# HTS221TR.net
KiCad netlist of a schematic drawn in EAGLE
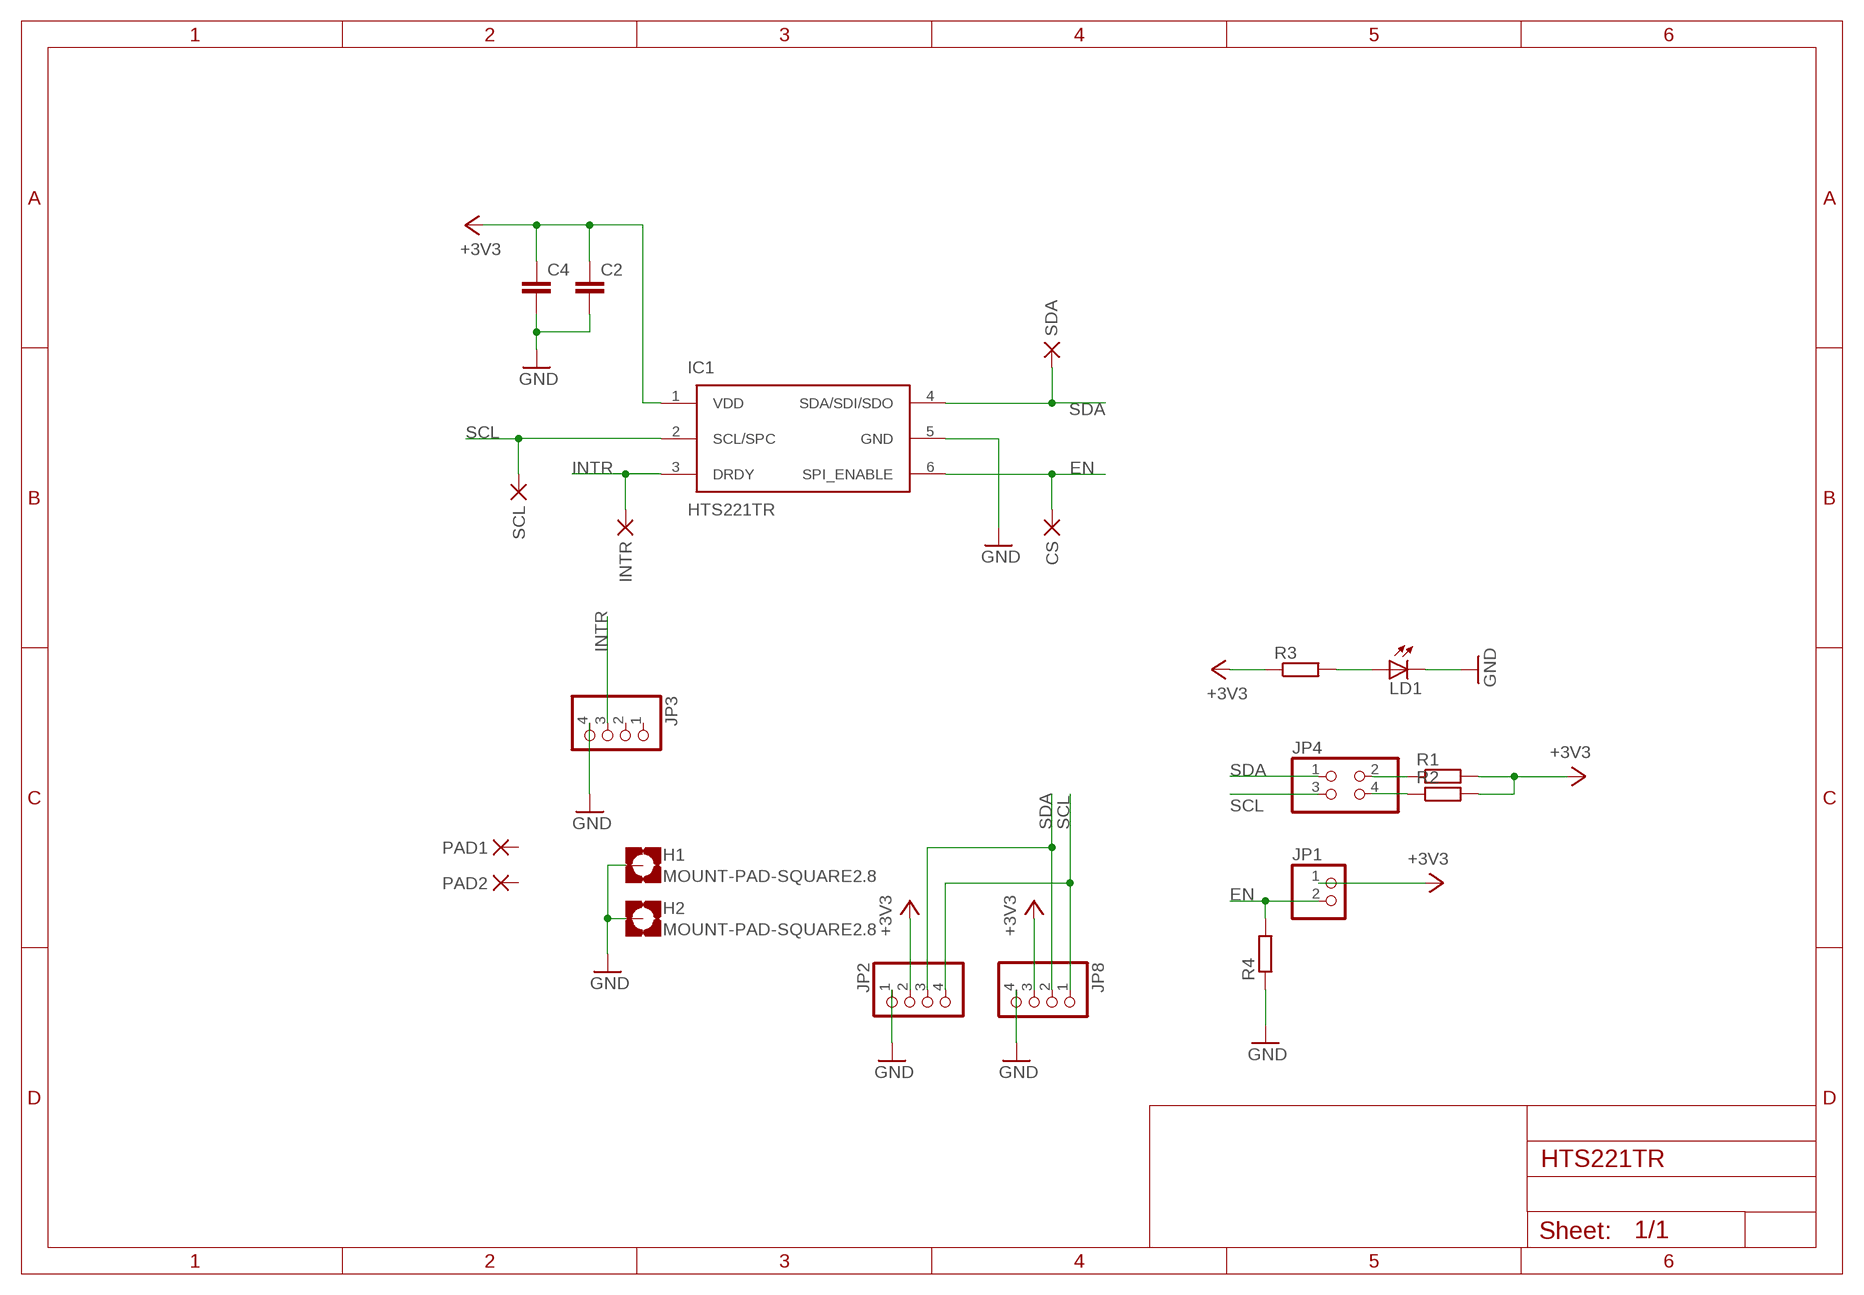
[diagram p0: schematic, sheet 1]

(export (version "E")
  (design (tool "Eeschema 10.0.6"))
  (components
    (comp (ref "C2")
      (value "C-EUC0805")
      (footprint "eagle-import:C0805")
      (libsource (lib "eagle-import") (part "C-EUC0805"))
    )
    (comp (ref "C4")
      (value "C-EUC0805")
      (footprint "eagle-import:C0805")
      (libsource (lib "eagle-import") (part "C-EUC0805"))
    )
    (comp (ref "CS")
      (value "PAD-SMD10R")
      (footprint "eagle-import:SMD10R")
      (libsource (lib "eagle-import") (part "PAD-SMD10R"))
    )
    (comp (ref "H1")
      (value "MOUNT-PAD-SQUARE2.8")
      (footprint "eagle-import:2,8-PAD-SQUARE")
      (libsource (lib "eagle-import") (part "MOUNT-PAD-SQUARE2.8"))
    )
    (comp (ref "H2")
      (value "MOUNT-PAD-SQUARE2.8")
      (footprint "eagle-import:2,8-PAD-SQUARE")
      (libsource (lib "eagle-import") (part "MOUNT-PAD-SQUARE2.8"))
    )
    (comp (ref "IC1")
      (value "HTS221TR")
      (footprint "eagle-import:HLGA-6L")
      (fields (field (name "MOUSER_PART_NUMBER") "511-HTS221TR") (field (name "RS_PART_NUMBER") "1660935"))
      (libsource (lib "eagle-import") (part "HTS221TR"))
    )
    (comp (ref "INTR")
      (value "PAD-SMD10R")
      (footprint "eagle-import:SMD10R")
      (libsource (lib "eagle-import") (part "PAD-SMD10R"))
    )
    (comp (ref "JP1")
      (value "PINHD-1X2")
      (footprint "eagle-import:1X02")
      (libsource (lib "eagle-import") (part "PINHD-1X2"))
    )
    (comp (ref "JP2")
      (value "PINHD-1X4_2.54-90°")
      (footprint "eagle-import:1X04_90")
      (libsource (lib "eagle-import") (part "PINHD-1X4_2.54-90°"))
    )
    (comp (ref "JP3")
      (value "PINHD-1X4")
      (footprint "eagle-import:1X04")
      (libsource (lib "eagle-import") (part "PINHD-1X4"))
    )
    (comp (ref "JP4")
      (value "PINHD-2X2_2.54")
      (footprint "eagle-import:2X02")
      (libsource (lib "eagle-import") (part "PINHD-2X2_2.54"))
    )
    (comp (ref "JP8")
      (value "PINHD-1X4_2.54-90°")
      (footprint "eagle-import:1X04_90")
      (libsource (lib "eagle-import") (part "PINHD-1X4_2.54-90°"))
    )
    (comp (ref "LD1")
      (value "LEDCHIPLED_0805")
      (footprint "eagle-import:CHIPLED_0805")
      (libsource (lib "eagle-import") (part "LEDCHIPLED_0805"))
    )
    (comp (ref "PAD1")
      (value "PAD-SMD10R")
      (footprint "eagle-import:SMD10R")
      (libsource (lib "eagle-import") (part "PAD-SMD10R"))
    )
    (comp (ref "PAD2")
      (value "PAD-SMD10R")
      (footprint "eagle-import:SMD10R")
      (libsource (lib "eagle-import") (part "PAD-SMD10R"))
    )
    (comp (ref "R1")
      (value "R-EU_R0805")
      (footprint "eagle-import:R0805")
      (libsource (lib "eagle-import") (part "R-EU_R0805"))
    )
    (comp (ref "R2")
      (value "R-EU_R0805")
      (footprint "eagle-import:R0805")
      (libsource (lib "eagle-import") (part "R-EU_R0805"))
    )
    (comp (ref "R3")
      (value "R-EU_R0805")
      (footprint "eagle-import:R0805")
      (libsource (lib "eagle-import") (part "R-EU_R0805"))
    )
    (comp (ref "R4")
      (value "R-EU_R0805")
      (footprint "eagle-import:R0805")
      (libsource (lib "eagle-import") (part "R-EU_R0805"))
    )
    (comp (ref "SCL")
      (value "PAD-SMD10R")
      (footprint "eagle-import:SMD10R")
      (libsource (lib "eagle-import") (part "PAD-SMD10R"))
    )
    (comp (ref "SDA")
      (value "PAD-SMD10R")
      (footprint "eagle-import:SMD10R")
      (libsource (lib "eagle-import") (part "PAD-SMD10R"))
    )
  )
  (nets
    (net (code "1") (name "+3V3") (class "Default")
      (node (ref "C2") (pin "1") (pinfunction "1_1") (pintype "passive"))
      (node (ref "C4") (pin "1") (pinfunction "1_1") (pintype "passive"))
      (node (ref "IC1") (pin "1") (pinfunction "VDD_1") (pintype "bidirectional"))
      (node (ref "JP1") (pin "1") (pinfunction "1_1") (pintype "passive"))
      (node (ref "JP2") (pin "2") (pinfunction "2_2") (pintype "passive"))
      (node (ref "JP8") (pin "3") (pinfunction "3_3") (pintype "passive"))
      (node (ref "R1") (pin "2") (pinfunction "2_2") (pintype "passive"))
      (node (ref "R2") (pin "2") (pinfunction "2_2") (pintype "passive"))
      (node (ref "R3") (pin "1") (pinfunction "1_1") (pintype "passive"))
    )
    (net (code "2") (name "/EN") (class "Default")
      (node (ref "CS") (pin "PAD") (pinfunction "P_PAD") (pintype "passive"))
      (node (ref "IC1") (pin "6") (pinfunction "SPI_ENABLE_6") (pintype "bidirectional"))
      (node (ref "JP1") (pin "2") (pinfunction "2_2") (pintype "passive"))
      (node (ref "R4") (pin "2") (pinfunction "2_2") (pintype "passive"))
    )
    (net (code "3") (name "/INTR") (class "Default")
      (node (ref "IC1") (pin "3") (pinfunction "DRDY_3") (pintype "bidirectional"))
      (node (ref "INTR") (pin "PAD") (pinfunction "P_PAD") (pintype "passive"))
      (node (ref "JP3") (pin "3") (pinfunction "3_3") (pintype "passive"))
    )
    (net (code "4") (name "/SCL") (class "Default")
      (node (ref "IC1") (pin "2") (pinfunction "SCL/SPC_2") (pintype "bidirectional"))
      (node (ref "JP2") (pin "4") (pinfunction "4_4") (pintype "passive"))
      (node (ref "JP4") (pin "3") (pinfunction "3_3") (pintype "passive"))
      (node (ref "JP8") (pin "1") (pinfunction "1_1") (pintype "passive"))
      (node (ref "SCL") (pin "PAD") (pinfunction "P_PAD") (pintype "passive"))
    )
    (net (code "5") (name "/SDA") (class "Default")
      (node (ref "IC1") (pin "4") (pinfunction "SDA/SDI/SDO_4") (pintype "bidirectional"))
      (node (ref "JP2") (pin "3") (pinfunction "3_3") (pintype "passive"))
      (node (ref "JP4") (pin "1") (pinfunction "1_1") (pintype "passive"))
      (node (ref "JP8") (pin "2") (pinfunction "2_2") (pintype "passive"))
      (node (ref "SDA") (pin "PAD") (pinfunction "P_PAD") (pintype "passive"))
    )
    (net (code "6") (name "GND") (class "Default")
      (node (ref "C2") (pin "2") (pinfunction "2_2") (pintype "passive"))
      (node (ref "C4") (pin "2") (pinfunction "2_2") (pintype "passive"))
      (node (ref "H1") (pin "B2,8") (pinfunction "MOUNT_B2,8") (pintype "passive"))
      (node (ref "H2") (pin "B2,8") (pinfunction "MOUNT_B2,8") (pintype "passive"))
      (node (ref "IC1") (pin "5") (pinfunction "GND_5") (pintype "bidirectional"))
      (node (ref "JP2") (pin "1") (pinfunction "1_1") (pintype "passive"))
      (node (ref "JP3") (pin "4") (pinfunction "4_4") (pintype "passive"))
      (node (ref "JP8") (pin "4") (pinfunction "4_4") (pintype "passive"))
      (node (ref "LD1") (pin "C") (pinfunction "C_C") (pintype "passive"))
      (node (ref "R4") (pin "1") (pinfunction "1_1") (pintype "passive"))
    )
    (net (code "7") (name "Net-(JP4-Pad2)") (class "Default")
      (node (ref "JP4") (pin "2") (pinfunction "2_2") (pintype "passive"))
      (node (ref "R1") (pin "1") (pinfunction "1_1") (pintype "passive"))
    )
    (net (code "8") (name "Net-(JP4-Pad4)") (class "Default")
      (node (ref "JP4") (pin "4") (pinfunction "4_4") (pintype "passive"))
      (node (ref "R2") (pin "1") (pinfunction "1_1") (pintype "passive"))
    )
    (net (code "9") (name "Net-(LD1-PadA)") (class "Default")
      (node (ref "LD1") (pin "A") (pinfunction "A_A") (pintype "passive"))
      (node (ref "R3") (pin "2") (pinfunction "2_2") (pintype "passive"))
    )
    (net (code "10") (name "unconnected-(JP3-Pad1)") (class "Default")
      (node (ref "JP3") (pin "1") (pinfunction "1_1") (pintype "passive"))
    )
    (net (code "11") (name "unconnected-(JP3-Pad2)") (class "Default")
      (node (ref "JP3") (pin "2") (pinfunction "2_2") (pintype "passive"))
    )
    (net (code "12") (name "unconnected-(PAD1-P-PadPAD)") (class "Default")
      (node (ref "PAD1") (pin "PAD") (pinfunction "P_PAD") (pintype "passive"))
    )
    (net (code "13") (name "unconnected-(PAD2-P-PadPAD)") (class "Default")
      (node (ref "PAD2") (pin "PAD") (pinfunction "P_PAD") (pintype "passive"))
    )
  )
)
